# MercurialSDR_FPGA_BNK.net
KiCad netlist of a schematic drawn in Altium Designer
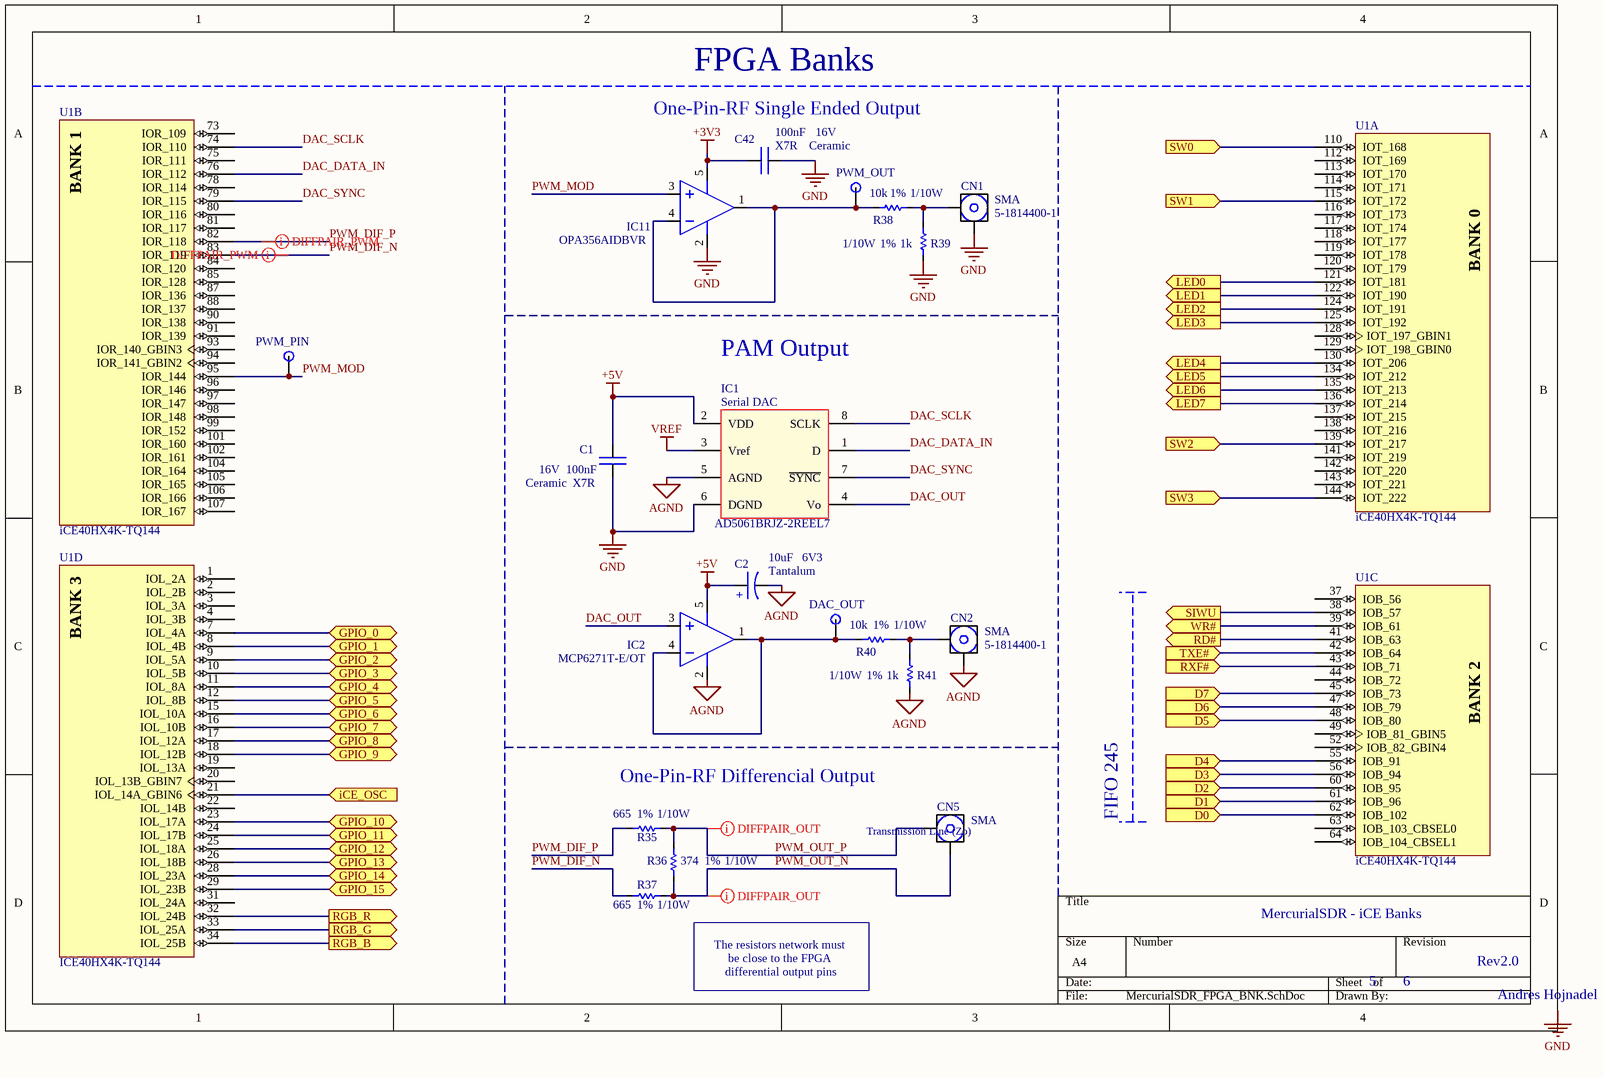
[diagram p0: MercurialSDR_FPGA_BNK.SchDoc]

(export (version "E")
  (design (tool "Eeschema 10.0.6"))
  (components
    (comp (ref "C1")
      (value "100nF")
      (footprint "CAP_0603")
      (description "Capacitor no polarizado")
      (fields
        (field (name "TEMP COEF") "X7R")
        (field (name "PART NUMBER") "CL10B104KO8NNNC")
        (field (name "VR") "16V")
        (field (name "MATERIAL") "Ceramic")
        (field (name "Comment") "Capacitor")
      )
      (libsource (lib "MercurialSDR") (part "Cap"))
    )
    (comp (ref "C2")
      (value "10uF")
      (footprint "CAP_TANT_1206")
      (description "Capacitor polarizado")
      (fields
        (field (name "PART NUMBER") "TAJA106K006RNJ")
        (field (name "VR") "6V3")
        (field (name "MATERIAL") "Tantalum")
        (field (name "Comment") "Capacitor Polarizado")
      )
      (libsource (lib "MercurialSDR") (part "Cap Pol"))
    )
    (comp (ref "C42")
      (value "100nF")
      (footprint "CAP_0603")
      (description "Capacitor no polarizado")
      (fields
        (field (name "TEMP COEF") "X7R")
        (field (name "PART NUMBER") "CL10B104KO8NNNC")
        (field (name "VR") "16V")
        (field (name "MATERIAL") "Ceramic")
        (field (name "Comment") "Capacitor")
      )
      (libsource (lib "MercurialSDR") (part "Cap"))
    )
    (comp (ref "CN1")
      (value "SMA")
      (footprint "SMA_Connector")
      (description "Conector SMA")
      (fields (field (name "PART NUMBER") "5-1814400-1"))
      (libsource (lib "MercurialSDR") (part "SMA"))
    )
    (comp (ref "CN2")
      (value "SMA")
      (footprint "SMA_Connector")
      (description "Conector SMA")
      (fields (field (name "PART NUMBER") "5-1814400-1"))
      (libsource (lib "MercurialSDR") (part "SMA"))
    )
    (comp (ref "CN5")
      (value "SMA")
      (footprint "SMA_Connector")
      (description "Conector SMA")
      (fields (field (name "PART NUMBER") "5-1814400-1"))
      (libsource (lib "MercurialSDR") (part "SMA"))
    )
    (comp (ref "IC1")
      (value "Serial DAC")
      (footprint "SOT-23-8")
      (description "DAC SPI")
      (fields (field (name "PART NUMBER") "AD5061BRJZ-2REEL7"))
      (libsource (lib "MercurialSDR") (part "AD5061"))
    )
    (comp (ref "IC2")
      (value "OPAMP")
      (footprint "SOT-23-5")
      (description "Operational Amplifier")
      (fields (field (name "PART NUMBER") "MCP6271T-E/OT"))
      (libsource (lib "MercurialSDR") (part "OPAMP"))
    )
    (comp (ref "IC11")
      (value "OPAMP")
      (footprint "SOT-23-5_2")
      (description "Operational Amplifier")
      (fields (field (name "PART NUMBER") "OPA356AIDBVR"))
      (libsource (lib "MercurialSDR") (part "OPAMP"))
    )
    (comp (ref "R35")
      (value "665")
      (footprint "RES_0603")
      (description "Resistor")
      (fields
        (field (name "POWER") "1/10W")
        (field (name "PART NUMBER") "RC0603FR-07665RL")
        (field (name "TOLERANCE") "1%")
        (field (name "Comment") "Resistor SMD")
      )
      (libsource (lib "MercurialSDR") (part "Res"))
    )
    (comp (ref "R36")
      (value "374")
      (footprint "RES_0603")
      (description "Resistor")
      (fields
        (field (name "POWER") "1/10W")
        (field (name "PART NUMBER") "RC0603FR-07374RL")
        (field (name "TOLERANCE") "1%")
        (field (name "Comment") "Resistor SMD")
      )
      (libsource (lib "MercurialSDR") (part "Res"))
    )
    (comp (ref "R37")
      (value "665")
      (footprint "RES_0603")
      (description "Resistor")
      (fields
        (field (name "POWER") "1/10W")
        (field (name "PART NUMBER") "RC0603FR-07665RL")
        (field (name "TOLERANCE") "1%")
        (field (name "Comment") "Resistor SMD")
      )
      (libsource (lib "MercurialSDR") (part "Res"))
    )
    (comp (ref "R38")
      (value "10k")
      (footprint "RES_0603")
      (description "Resistor")
      (fields
        (field (name "POWER") "1/10W")
        (field (name "PART NUMBER") "CR0603-FX-1002EAS")
        (field (name "TOLERANCE") "1%")
        (field (name "Comment") "Resistor SMD")
      )
      (libsource (lib "MercurialSDR") (part "Res"))
    )
    (comp (ref "R39")
      (value "1k")
      (footprint "RES_0603")
      (description "Resistor")
      (fields
        (field (name "POWER") "1/10W")
        (field (name "PART NUMBER") "CR0603-FX-1001ELF")
        (field (name "TOLERANCE") "1%")
        (field (name "Comment") "Resistor SMD")
      )
      (libsource (lib "MercurialSDR") (part "Res"))
    )
    (comp (ref "R40")
      (value "10k")
      (footprint "RES_0603")
      (description "Resistor")
      (fields
        (field (name "POWER") "1/10W")
        (field (name "PART NUMBER") "CR0603-FX-1002EAS")
        (field (name "TOLERANCE") "1%")
        (field (name "Comment") "Resistor SMD")
      )
      (libsource (lib "MercurialSDR") (part "Res"))
    )
    (comp (ref "R41")
      (value "1k")
      (footprint "RES_0603")
      (description "Resistor")
      (fields
        (field (name "POWER") "1/10W")
        (field (name "PART NUMBER") "CR0603-FX-1001ELF")
        (field (name "TOLERANCE") "1%")
        (field (name "Comment") "Resistor SMD")
      )
      (libsource (lib "MercurialSDR") (part "Res"))
    )
    (comp (ref "TP1")
      (value "Test Point")
      (footprint "TP_TOP")
      (fields (field (name "TP NAME") "PWM_PIN"))
      (libsource (lib "MercurialSDR") (part "Test Point"))
    )
    (comp (ref "TP2")
      (value "Test Point")
      (footprint "TP_TH")
      (fields (field (name "TP NAME") "DAC_OUT"))
      (libsource (lib "MercurialSDR") (part "Test Point"))
    )
    (comp (ref "TP5")
      (value "Test Point")
      (footprint "TP_TH")
      (fields (field (name "TP NAME") "PWM_OUT"))
      (libsource (lib "MercurialSDR") (part "Test Point"))
    )
    (comp (ref "U1")
      (value "iCE40HX4K-TQ144")
      (footprint "LATC-TQFP-144_L")
      (fields
        (field (name "PARTNUMBER") "ICE40HX4K-TQ144")
        (field (name "MANUFACTURER") "Lattice Semiconductor")
      )
      (libsource (lib "MercurialSDR") (part "ICE40HX4K-TQ144"))
    )
  )
  (nets
    (net (code "1") (name "+3V3") (class "Default")
      (node (ref "C42") (pin "2") (pinfunction "2_2") (pintype "passive"))
      (node (ref "IC11") (pin "5") (pinfunction "VDD_5") (pintype "passive"))
    )
    (net (code "2") (name "+5V") (class "Default")
      (node (ref "C1") (pin "1") (pinfunction "1_1") (pintype "passive"))
      (node (ref "C2") (pin "1") (pinfunction "1_1") (pintype "passive"))
      (node (ref "IC1") (pin "2") (pinfunction "VDD_2") (pintype "passive"))
      (node (ref "IC2") (pin "5") (pinfunction "VDD_5") (pintype "passive"))
    )
    (net (code "3") (name "/D0") (class "Default")
      (node (ref "U1") (pin "62") (pinfunction "IOB_102_62") (pintype "bidirectional"))
    )
    (net (code "4") (name "/D1") (class "Default")
      (node (ref "U1") (pin "61") (pinfunction "IOB_96_61") (pintype "bidirectional"))
    )
    (net (code "5") (name "/D2") (class "Default")
      (node (ref "U1") (pin "60") (pinfunction "IOB_95_60") (pintype "bidirectional"))
    )
    (net (code "6") (name "/D3") (class "Default")
      (node (ref "U1") (pin "56") (pinfunction "IOB_94_56") (pintype "bidirectional"))
    )
    (net (code "7") (name "/D4") (class "Default")
      (node (ref "U1") (pin "55") (pinfunction "IOB_91_55") (pintype "bidirectional"))
    )
    (net (code "8") (name "/D5") (class "Default")
      (node (ref "U1") (pin "48") (pinfunction "IOB_80_48") (pintype "bidirectional"))
    )
    (net (code "9") (name "/D6") (class "Default")
      (node (ref "U1") (pin "47") (pinfunction "IOB_79_47") (pintype "bidirectional"))
    )
    (net (code "10") (name "/D7") (class "Default")
      (node (ref "U1") (pin "45") (pinfunction "IOB_73_45") (pintype "bidirectional"))
    )
    (net (code "11") (name "/DAC_DATA_IN") (class "Default")
      (node (ref "IC1") (pin "1") (pinfunction "D_1") (pintype "passive"))
      (node (ref "U1") (pin "76") (pinfunction "IOR_112_76") (pintype "bidirectional"))
    )
    (net (code "12") (name "/DAC_OUT") (class "Default")
      (node (ref "IC1") (pin "4") (pinfunction "Vo_4") (pintype "passive"))
      (node (ref "IC2") (pin "3") (pinfunction "V+_3") (pintype "passive"))
    )
    (net (code "13") (name "/DAC_SCLK") (class "Default")
      (node (ref "IC1") (pin "8") (pinfunction "SCLK_8") (pintype "passive"))
      (node (ref "U1") (pin "74") (pinfunction "IOR_110_74") (pintype "bidirectional"))
    )
    (net (code "14") (name "/DAC_SYNC") (class "Default")
      (node (ref "IC1") (pin "7") (pinfunction "~{SYNC}_7") (pintype "passive"))
      (node (ref "U1") (pin "79") (pinfunction "IOR_115_79") (pintype "bidirectional"))
    )
    (net (code "15") (name "/GPIO_0") (class "Default")
      (node (ref "U1") (pin "7") (pinfunction "IOL_4A_7") (pintype "bidirectional"))
    )
    (net (code "16") (name "/GPIO_1") (class "Default")
      (node (ref "U1") (pin "8") (pinfunction "IOL_4B_8") (pintype "bidirectional"))
    )
    (net (code "17") (name "/GPIO_2") (class "Default")
      (node (ref "U1") (pin "9") (pinfunction "IOL_5A_9") (pintype "bidirectional"))
    )
    (net (code "18") (name "/GPIO_3") (class "Default")
      (node (ref "U1") (pin "10") (pinfunction "IOL_5B_10") (pintype "bidirectional"))
    )
    (net (code "19") (name "/GPIO_4") (class "Default")
      (node (ref "U1") (pin "11") (pinfunction "IOL_8A_11") (pintype "bidirectional"))
    )
    (net (code "20") (name "/GPIO_5") (class "Default")
      (node (ref "U1") (pin "12") (pinfunction "IOL_8B_12") (pintype "bidirectional"))
    )
    (net (code "21") (name "/GPIO_6") (class "Default")
      (node (ref "U1") (pin "15") (pinfunction "IOL_10A_15") (pintype "bidirectional"))
    )
    (net (code "22") (name "/GPIO_7") (class "Default")
      (node (ref "U1") (pin "16") (pinfunction "IOL_10B_16") (pintype "bidirectional"))
    )
    (net (code "23") (name "/GPIO_8") (class "Default")
      (node (ref "U1") (pin "17") (pinfunction "IOL_12A_17") (pintype "bidirectional"))
    )
    (net (code "24") (name "/GPIO_9") (class "Default")
      (node (ref "U1") (pin "18") (pinfunction "IOL_12B_18") (pintype "bidirectional"))
    )
    (net (code "25") (name "/GPIO_10") (class "Default")
      (node (ref "U1") (pin "23") (pinfunction "IOL_17A_23") (pintype "bidirectional"))
    )
    (net (code "26") (name "/GPIO_11") (class "Default")
      (node (ref "U1") (pin "24") (pinfunction "IOL_17B_24") (pintype "bidirectional"))
    )
    (net (code "27") (name "/GPIO_12") (class "Default")
      (node (ref "U1") (pin "25") (pinfunction "IOL_18A_25") (pintype "bidirectional"))
    )
    (net (code "28") (name "/GPIO_13") (class "Default")
      (node (ref "U1") (pin "26") (pinfunction "IOL_18B_26") (pintype "bidirectional"))
    )
    (net (code "29") (name "/GPIO_14") (class "Default")
      (node (ref "U1") (pin "28") (pinfunction "IOL_23A_28") (pintype "bidirectional"))
    )
    (net (code "30") (name "/GPIO_15") (class "Default")
      (node (ref "U1") (pin "29") (pinfunction "IOL_23B_29") (pintype "bidirectional"))
    )
    (net (code "31") (name "/LED0") (class "Default")
      (node (ref "U1") (pin "121") (pinfunction "IOT_181_121") (pintype "bidirectional"))
    )
    (net (code "32") (name "/LED1") (class "Default")
      (node (ref "U1") (pin "122") (pinfunction "IOT_190_122") (pintype "bidirectional"))
    )
    (net (code "33") (name "/LED2") (class "Default")
      (node (ref "U1") (pin "124") (pinfunction "IOT_191_124") (pintype "bidirectional"))
    )
    (net (code "34") (name "/LED3") (class "Default")
      (node (ref "U1") (pin "125") (pinfunction "IOT_192_125") (pintype "bidirectional"))
    )
    (net (code "35") (name "/LED4") (class "Default")
      (node (ref "U1") (pin "130") (pinfunction "IOT_206_130") (pintype "bidirectional"))
    )
    (net (code "36") (name "/LED5") (class "Default")
      (node (ref "U1") (pin "134") (pinfunction "IOT_212_134") (pintype "bidirectional"))
    )
    (net (code "37") (name "/LED6") (class "Default")
      (node (ref "U1") (pin "135") (pinfunction "IOT_213_135") (pintype "bidirectional"))
    )
    (net (code "38") (name "/LED7") (class "Default")
      (node (ref "U1") (pin "136") (pinfunction "IOT_214_136") (pintype "bidirectional"))
    )
    (net (code "39") (name "/PWM_DIF_N") (class "Default")
      (node (ref "R37") (pin "2") (pinfunction "2_2") (pintype "passive"))
      (node (ref "U1") (pin "83") (pinfunction "IOR_119_83") (pintype "bidirectional"))
    )
    (net (code "40") (name "/PWM_DIF_P") (class "Default")
      (node (ref "R35") (pin "2") (pinfunction "2_2") (pintype "passive"))
      (node (ref "U1") (pin "82") (pinfunction "IOR_118_82") (pintype "bidirectional"))
    )
    (net (code "41") (name "/PWM_MOD") (class "Default")
      (node (ref "IC11") (pin "3") (pinfunction "V+_3") (pintype "passive"))
      (node (ref "TP1") (pin "1") (pinfunction "TP?_1") (pintype "passive"))
      (node (ref "U1") (pin "95") (pinfunction "IOR_144_95") (pintype "bidirectional"))
    )
    (net (code "42") (name "/PWM_OUT_N") (class "Default")
      (node (ref "CN5") (pin "2") (pinfunction "GND_2") (pintype "passive"))
      (node (ref "R36") (pin "2") (pinfunction "2_2") (pintype "passive"))
      (node (ref "R37") (pin "1") (pinfunction "1_1") (pintype "passive"))
    )
    (net (code "43") (name "/PWM_OUT_P") (class "Default")
      (node (ref "CN5") (pin "1") (pinfunction "Vin_1") (pintype "passive"))
      (node (ref "R35") (pin "1") (pinfunction "1_1") (pintype "passive"))
      (node (ref "R36") (pin "1") (pinfunction "1_1") (pintype "passive"))
    )
    (net (code "44") (name "/RD#") (class "Default")
      (node (ref "U1") (pin "41") (pinfunction "IOB_63_41") (pintype "bidirectional"))
    )
    (net (code "45") (name "/RGB_B") (class "Default")
      (node (ref "U1") (pin "34") (pinfunction "IOL_25B_34") (pintype "bidirectional"))
    )
    (net (code "46") (name "/RGB_G") (class "Default")
      (node (ref "U1") (pin "33") (pinfunction "IOL_25A_33") (pintype "bidirectional"))
    )
    (net (code "47") (name "/RGB_R") (class "Default")
      (node (ref "U1") (pin "32") (pinfunction "IOL_24B_32") (pintype "bidirectional"))
    )
    (net (code "48") (name "/RXF#") (class "Default")
      (node (ref "U1") (pin "43") (pinfunction "IOB_71_43") (pintype "bidirectional"))
    )
    (net (code "49") (name "/SIWU") (class "Default")
      (node (ref "U1") (pin "38") (pinfunction "IOB_57_38") (pintype "bidirectional"))
    )
    (net (code "50") (name "/SW0") (class "Default")
      (node (ref "U1") (pin "110") (pinfunction "IOT_168_110") (pintype "bidirectional"))
    )
    (net (code "51") (name "/SW1") (class "Default")
      (node (ref "U1") (pin "115") (pinfunction "IOT_172_115") (pintype "bidirectional"))
    )
    (net (code "52") (name "/SW2") (class "Default")
      (node (ref "U1") (pin "139") (pinfunction "IOT_217_139") (pintype "bidirectional"))
    )
    (net (code "53") (name "/SW3") (class "Default")
      (node (ref "U1") (pin "144") (pinfunction "IOT_222_144") (pintype "bidirectional"))
    )
    (net (code "54") (name "/TXE#") (class "Default")
      (node (ref "U1") (pin "42") (pinfunction "IOB_64_42") (pintype "bidirectional"))
    )
    (net (code "55") (name "/WR#") (class "Default")
      (node (ref "U1") (pin "39") (pinfunction "IOB_61_39") (pintype "bidirectional"))
    )
    (net (code "56") (name "/iCE_OSC") (class "Default")
      (node (ref "U1") (pin "21") (pinfunction "IOL_14A_GBIN6_21") (pintype "bidirectional"))
    )
    (net (code "57") (name "AGND") (class "Default")
      (node (ref "C2") (pin "2") (pinfunction "2_2") (pintype "passive"))
      (node (ref "CN2") (pin "2") (pinfunction "GND_2") (pintype "passive"))
      (node (ref "IC1") (pin "5") (pinfunction "AGND_5") (pintype "passive"))
      (node (ref "IC2") (pin "2") (pinfunction "Vss_2") (pintype "passive"))
      (node (ref "R41") (pin "2") (pinfunction "2_2") (pintype "passive"))
    )
    (net (code "58") (name "GND") (class "Default")
      (node (ref "C1") (pin "2") (pinfunction "2_2") (pintype "passive"))
      (node (ref "C42") (pin "1") (pinfunction "1_1") (pintype "passive"))
      (node (ref "CN1") (pin "2") (pinfunction "GND_2") (pintype "passive"))
      (node (ref "IC1") (pin "6") (pinfunction "DGND_6") (pintype "passive"))
      (node (ref "IC11") (pin "2") (pinfunction "Vss_2") (pintype "passive"))
      (node (ref "R39") (pin "2") (pinfunction "2_2") (pintype "passive"))
    )
    (net (code "59") (name "Net-(CN1-Vin)") (class "Default")
      (node (ref "CN1") (pin "1") (pinfunction "Vin_1") (pintype "passive"))
      (node (ref "R38") (pin "2") (pinfunction "2_2") (pintype "passive"))
      (node (ref "R39") (pin "1") (pinfunction "1_1") (pintype "passive"))
    )
    (net (code "60") (name "Net-(CN2-Vin)") (class "Default")
      (node (ref "CN2") (pin "1") (pinfunction "Vin_1") (pintype "passive"))
      (node (ref "R40") (pin "2") (pinfunction "2_2") (pintype "passive"))
      (node (ref "R41") (pin "1") (pinfunction "1_1") (pintype "passive"))
    )
    (net (code "61") (name "Net-(IC2-V-)") (class "Default")
      (node (ref "IC2") (pin "1") (pinfunction "Vo_1") (pintype "passive"))
      (node (ref "IC2") (pin "4") (pinfunction "V-_4") (pintype "passive"))
      (node (ref "R40") (pin "1") (pinfunction "1_1") (pintype "passive"))
      (node (ref "TP2") (pin "1") (pinfunction "TP?_1") (pintype "passive"))
    )
    (net (code "62") (name "Net-(IC11-V-)") (class "Default")
      (node (ref "IC11") (pin "1") (pinfunction "Vo_1") (pintype "passive"))
      (node (ref "IC11") (pin "4") (pinfunction "V-_4") (pintype "passive"))
      (node (ref "R38") (pin "1") (pinfunction "1_1") (pintype "passive"))
      (node (ref "TP5") (pin "1") (pinfunction "TP?_1") (pintype "passive"))
    )
    (net (code "63") (name "VREF") (class "Default")
      (node (ref "IC1") (pin "3") (pinfunction "Vref_3") (pintype "passive"))
    )
    (net (code "64") (name "unconnected-(U1A-IOT_169-Pad112)") (class "Default")
      (node (ref "U1") (pin "112") (pinfunction "IOT_169_112") (pintype "bidirectional"))
    )
    (net (code "65") (name "unconnected-(U1A-IOT_170-Pad113)") (class "Default")
      (node (ref "U1") (pin "113") (pinfunction "IOT_170_113") (pintype "bidirectional"))
    )
    (net (code "66") (name "unconnected-(U1A-IOT_171-Pad114)") (class "Default")
      (node (ref "U1") (pin "114") (pinfunction "IOT_171_114") (pintype "bidirectional"))
    )
    (net (code "67") (name "unconnected-(U1A-IOT_173-Pad116)") (class "Default")
      (node (ref "U1") (pin "116") (pinfunction "IOT_173_116") (pintype "bidirectional"))
    )
    (net (code "68") (name "unconnected-(U1A-IOT_174-Pad117)") (class "Default")
      (node (ref "U1") (pin "117") (pinfunction "IOT_174_117") (pintype "bidirectional"))
    )
    (net (code "69") (name "unconnected-(U1A-IOT_177-Pad118)") (class "Default")
      (node (ref "U1") (pin "118") (pinfunction "IOT_177_118") (pintype "bidirectional"))
    )
    (net (code "70") (name "unconnected-(U1A-IOT_178-Pad119)") (class "Default")
      (node (ref "U1") (pin "119") (pinfunction "IOT_178_119") (pintype "bidirectional"))
    )
    (net (code "71") (name "unconnected-(U1A-IOT_179-Pad120)") (class "Default")
      (node (ref "U1") (pin "120") (pinfunction "IOT_179_120") (pintype "bidirectional"))
    )
    (net (code "72") (name "unconnected-(U1A-IOT_197_GBIN1-Pad128)") (class "Default")
      (node (ref "U1") (pin "128") (pinfunction "IOT_197_GBIN1_128") (pintype "bidirectional"))
    )
    (net (code "73") (name "unconnected-(U1A-IOT_198_GBIN0-Pad129)") (class "Default")
      (node (ref "U1") (pin "129") (pinfunction "IOT_198_GBIN0_129") (pintype "bidirectional"))
    )
    (net (code "74") (name "unconnected-(U1A-IOT_215-Pad137)") (class "Default")
      (node (ref "U1") (pin "137") (pinfunction "IOT_215_137") (pintype "bidirectional"))
    )
    (net (code "75") (name "unconnected-(U1A-IOT_216-Pad138)") (class "Default")
      (node (ref "U1") (pin "138") (pinfunction "IOT_216_138") (pintype "bidirectional"))
    )
    (net (code "76") (name "unconnected-(U1A-IOT_219-Pad141)") (class "Default")
      (node (ref "U1") (pin "141") (pinfunction "IOT_219_141") (pintype "bidirectional"))
    )
    (net (code "77") (name "unconnected-(U1A-IOT_220-Pad142)") (class "Default")
      (node (ref "U1") (pin "142") (pinfunction "IOT_220_142") (pintype "bidirectional"))
    )
    (net (code "78") (name "unconnected-(U1A-IOT_221-Pad143)") (class "Default")
      (node (ref "U1") (pin "143") (pinfunction "IOT_221_143") (pintype "bidirectional"))
    )
    (net (code "79") (name "unconnected-(U1B-IOR_109-Pad73)") (class "Default")
      (node (ref "U1") (pin "73") (pinfunction "IOR_109_73") (pintype "bidirectional"))
    )
    (net (code "80") (name "unconnected-(U1B-IOR_111-Pad75)") (class "Default")
      (node (ref "U1") (pin "75") (pinfunction "IOR_111_75") (pintype "bidirectional"))
    )
    (net (code "81") (name "unconnected-(U1B-IOR_114-Pad78)") (class "Default")
      (node (ref "U1") (pin "78") (pinfunction "IOR_114_78") (pintype "bidirectional"))
    )
    (net (code "82") (name "unconnected-(U1B-IOR_116-Pad80)") (class "Default")
      (node (ref "U1") (pin "80") (pinfunction "IOR_116_80") (pintype "bidirectional"))
    )
    (net (code "83") (name "unconnected-(U1B-IOR_117-Pad81)") (class "Default")
      (node (ref "U1") (pin "81") (pinfunction "IOR_117_81") (pintype "bidirectional"))
    )
    (net (code "84") (name "unconnected-(U1B-IOR_120-Pad84)") (class "Default")
      (node (ref "U1") (pin "84") (pinfunction "IOR_120_84") (pintype "bidirectional"))
    )
    (net (code "85") (name "unconnected-(U1B-IOR_128-Pad85)") (class "Default")
      (node (ref "U1") (pin "85") (pinfunction "IOR_128_85") (pintype "bidirectional"))
    )
    (net (code "86") (name "unconnected-(U1B-IOR_136-Pad87)") (class "Default")
      (node (ref "U1") (pin "87") (pinfunction "IOR_136_87") (pintype "bidirectional"))
    )
    (net (code "87") (name "unconnected-(U1B-IOR_137-Pad88)") (class "Default")
      (node (ref "U1") (pin "88") (pinfunction "IOR_137_88") (pintype "bidirectional"))
    )
    (net (code "88") (name "unconnected-(U1B-IOR_138-Pad90)") (class "Default")
      (node (ref "U1") (pin "90") (pinfunction "IOR_138_90") (pintype "bidirectional"))
    )
    (net (code "89") (name "unconnected-(U1B-IOR_139-Pad91)") (class "Default")
      (node (ref "U1") (pin "91") (pinfunction "IOR_139_91") (pintype "bidirectional"))
    )
    (net (code "90") (name "unconnected-(U1B-IOR_140_GBIN3-Pad93)") (class "Default")
      (node (ref "U1") (pin "93") (pinfunction "IOR_140_GBIN3_93") (pintype "bidirectional"))
    )
    (net (code "91") (name "unconnected-(U1B-IOR_141_GBIN2-Pad94)") (class "Default")
      (node (ref "U1") (pin "94") (pinfunction "IOR_141_GBIN2_94") (pintype "bidirectional"))
    )
    (net (code "92") (name "unconnected-(U1B-IOR_146-Pad96)") (class "Default")
      (node (ref "U1") (pin "96") (pinfunction "IOR_146_96") (pintype "bidirectional"))
    )
    (net (code "93") (name "unconnected-(U1B-IOR_147-Pad97)") (class "Default")
      (node (ref "U1") (pin "97") (pinfunction "IOR_147_97") (pintype "bidirectional"))
    )
    (net (code "94") (name "unconnected-(U1B-IOR_148-Pad98)") (class "Default")
      (node (ref "U1") (pin "98") (pinfunction "IOR_148_98") (pintype "bidirectional"))
    )
    (net (code "95") (name "unconnected-(U1B-IOR_152-Pad99)") (class "Default")
      (node (ref "U1") (pin "99") (pinfunction "IOR_152_99") (pintype "bidirectional"))
    )
    (net (code "96") (name "unconnected-(U1B-IOR_160-Pad101)") (class "Default")
      (node (ref "U1") (pin "101") (pinfunction "IOR_160_101") (pintype "bidirectional"))
    )
    (net (code "97") (name "unconnected-(U1B-IOR_161-Pad102)") (class "Default")
      (node (ref "U1") (pin "102") (pinfunction "IOR_161_102") (pintype "bidirectional"))
    )
    (net (code "98") (name "unconnected-(U1B-IOR_164-Pad104)") (class "Default")
      (node (ref "U1") (pin "104") (pinfunction "IOR_164_104") (pintype "bidirectional"))
    )
    (net (code "99") (name "unconnected-(U1B-IOR_165-Pad105)") (class "Default")
      (node (ref "U1") (pin "105") (pinfunction "IOR_165_105") (pintype "bidirectional"))
    )
    (net (code "100") (name "unconnected-(U1B-IOR_166-Pad106)") (class "Default")
      (node (ref "U1") (pin "106") (pinfunction "IOR_166_106") (pintype "bidirectional"))
    )
    (net (code "101") (name "unconnected-(U1B-IOR_167-Pad107)") (class "Default")
      (node (ref "U1") (pin "107") (pinfunction "IOR_167_107") (pintype "bidirectional"))
    )
    (net (code "102") (name "unconnected-(U1C-IOB_56-Pad37)") (class "Default")
      (node (ref "U1") (pin "37") (pinfunction "IOB_56_37") (pintype "bidirectional"))
    )
    (net (code "103") (name "unconnected-(U1C-IOB_72-Pad44)") (class "Default")
      (node (ref "U1") (pin "44") (pinfunction "IOB_72_44") (pintype "bidirectional"))
    )
    (net (code "104") (name "unconnected-(U1C-IOB_81_GBIN5-Pad49)") (class "Default")
      (node (ref "U1") (pin "49") (pinfunction "IOB_81_GBIN5_49") (pintype "bidirectional"))
    )
    (net (code "105") (name "unconnected-(U1C-IOB_82_GBIN4-Pad52)") (class "Default")
      (node (ref "U1") (pin "52") (pinfunction "IOB_82_GBIN4_52") (pintype "bidirectional"))
    )
    (net (code "106") (name "unconnected-(U1C-IOB_103_CBSEL0-Pad63)") (class "Default")
      (node (ref "U1") (pin "63") (pinfunction "IOB_103_CBSEL0_63") (pintype "bidirectional"))
    )
    (net (code "107") (name "unconnected-(U1C-IOB_104_CBSEL1-Pad64)") (class "Default")
      (node (ref "U1") (pin "64") (pinfunction "IOB_104_CBSEL1_64") (pintype "bidirectional"))
    )
    (net (code "108") (name "unconnected-(U1D-IOL_2A-Pad1)") (class "Default")
      (node (ref "U1") (pin "1") (pinfunction "IOL_2A_1") (pintype "bidirectional"))
    )
    (net (code "109") (name "unconnected-(U1D-IOL_2B-Pad2)") (class "Default")
      (node (ref "U1") (pin "2") (pinfunction "IOL_2B_2") (pintype "bidirectional"))
    )
    (net (code "110") (name "unconnected-(U1D-IOL_3A-Pad3)") (class "Default")
      (node (ref "U1") (pin "3") (pinfunction "IOL_3A_3") (pintype "bidirectional"))
    )
    (net (code "111") (name "unconnected-(U1D-IOL_3B-Pad4)") (class "Default")
      (node (ref "U1") (pin "4") (pinfunction "IOL_3B_4") (pintype "bidirectional"))
    )
    (net (code "112") (name "unconnected-(U1D-IOL_13A-Pad19)") (class "Default")
      (node (ref "U1") (pin "19") (pinfunction "IOL_13A_19") (pintype "bidirectional"))
    )
    (net (code "113") (name "unconnected-(U1D-IOL_13B_GBIN7-Pad20)") (class "Default")
      (node (ref "U1") (pin "20") (pinfunction "IOL_13B_GBIN7_20") (pintype "bidirectional"))
    )
    (net (code "114") (name "unconnected-(U1D-IOL_14B-Pad22)") (class "Default")
      (node (ref "U1") (pin "22") (pinfunction "IOL_14B_22") (pintype "bidirectional"))
    )
    (net (code "115") (name "unconnected-(U1D-IOL_24A-Pad31)") (class "Default")
      (node (ref "U1") (pin "31") (pinfunction "IOL_24A_31") (pintype "bidirectional"))
    )
  )
)
